# shield_2x_driver.net
KiCad netlist of a schematic drawn in EAGLE
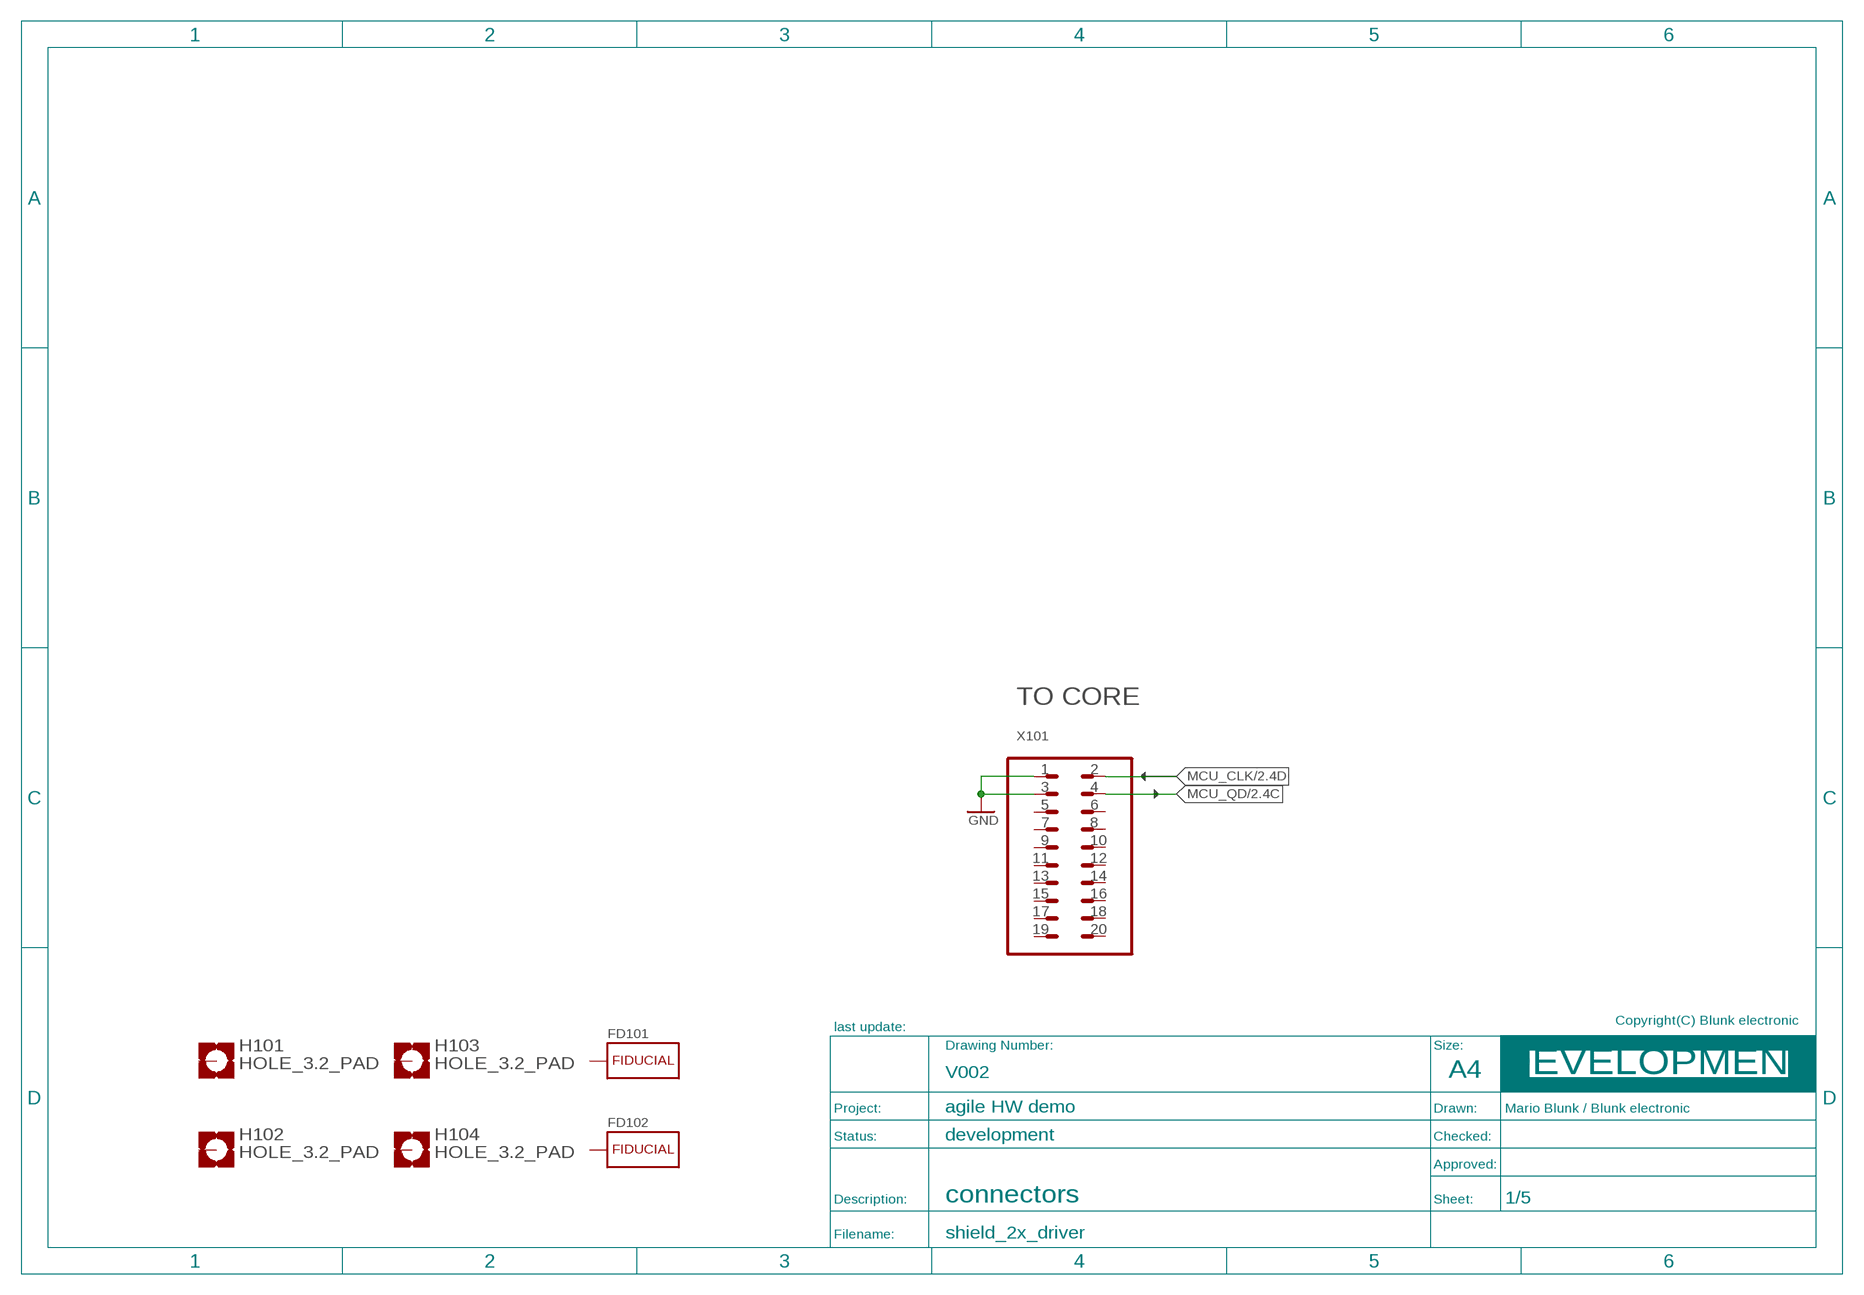
[diagram p0: schematic, sheet 1]
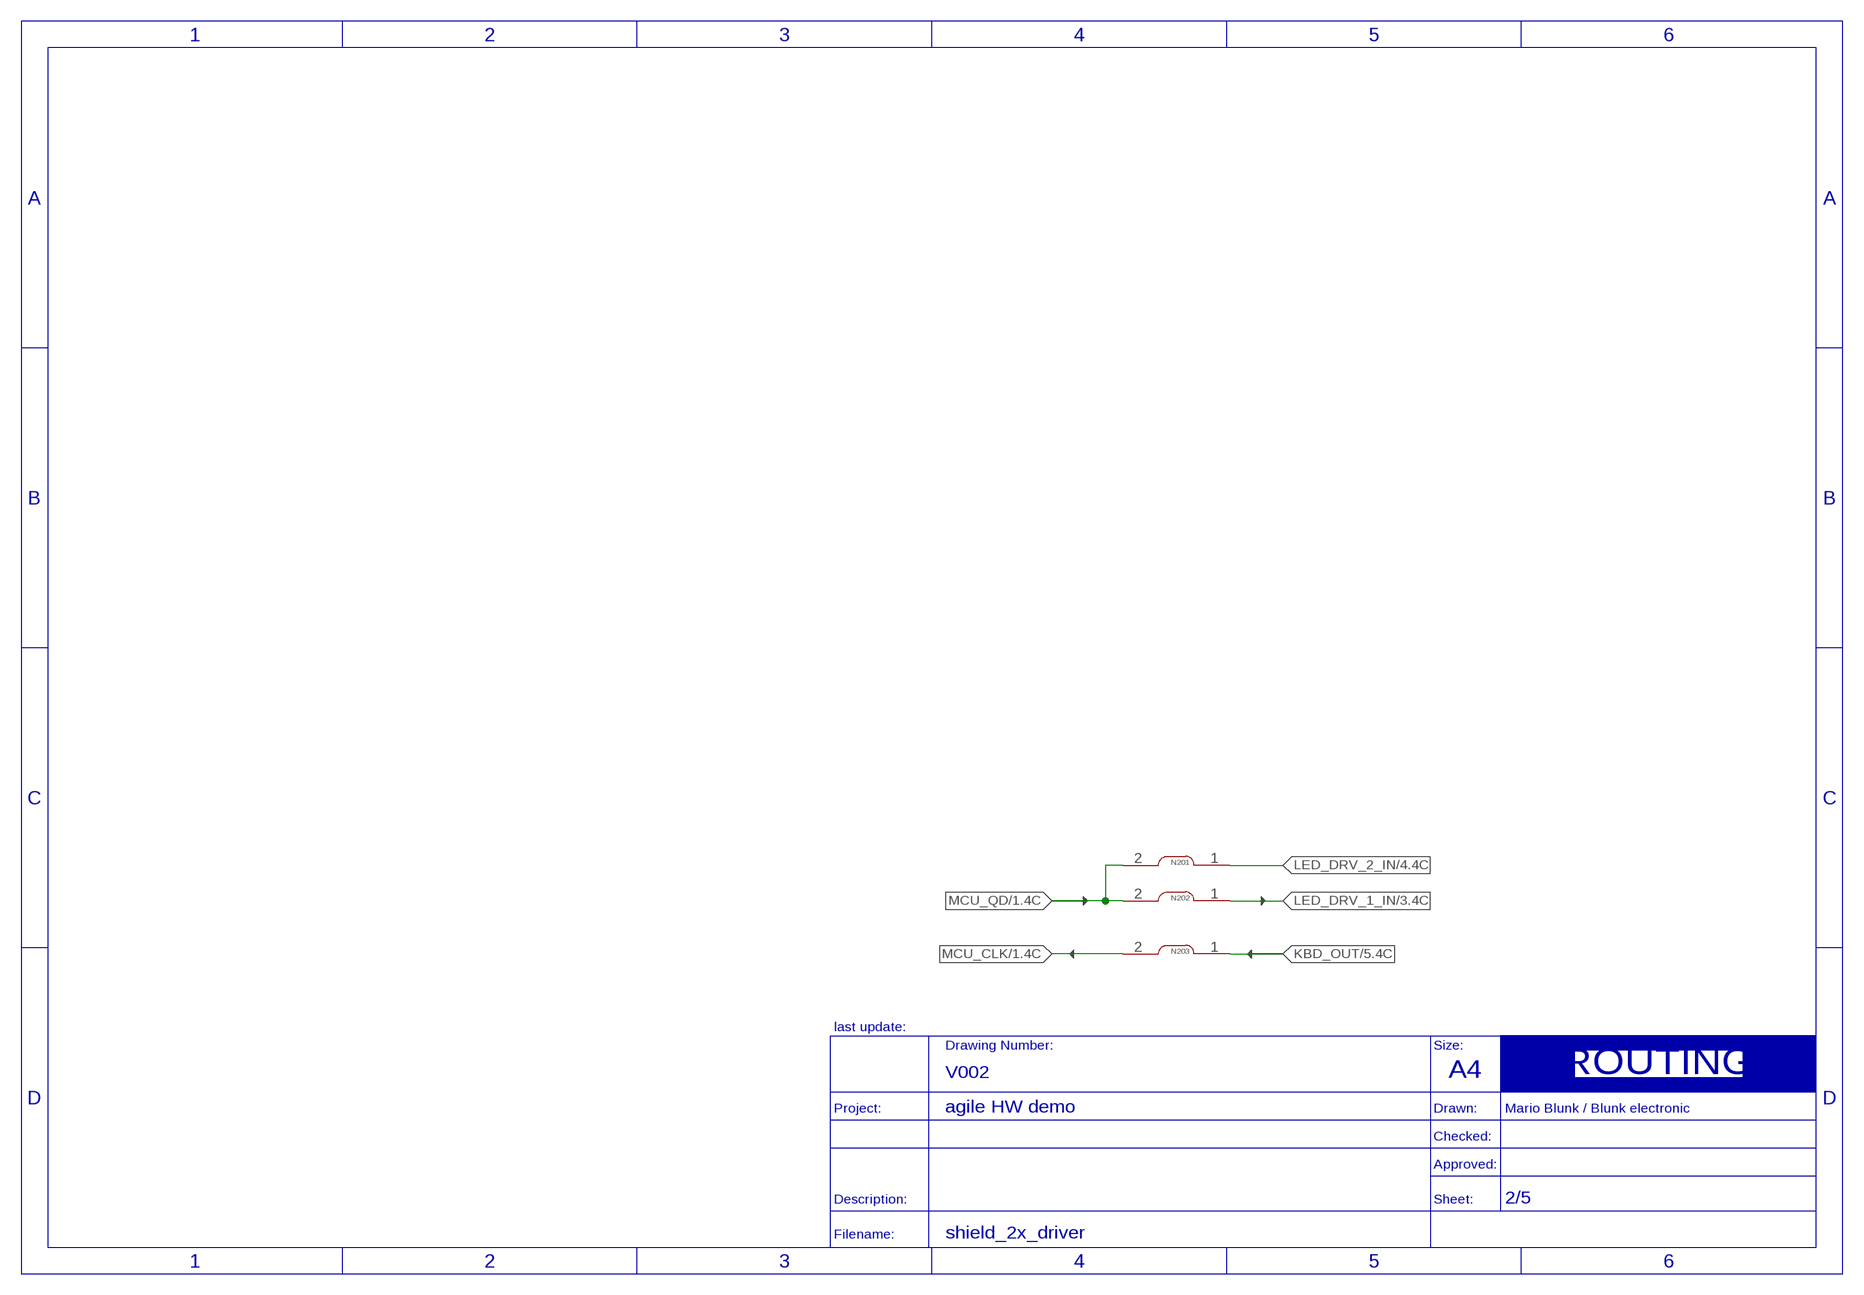
[diagram p1: schematic, sheet 2]
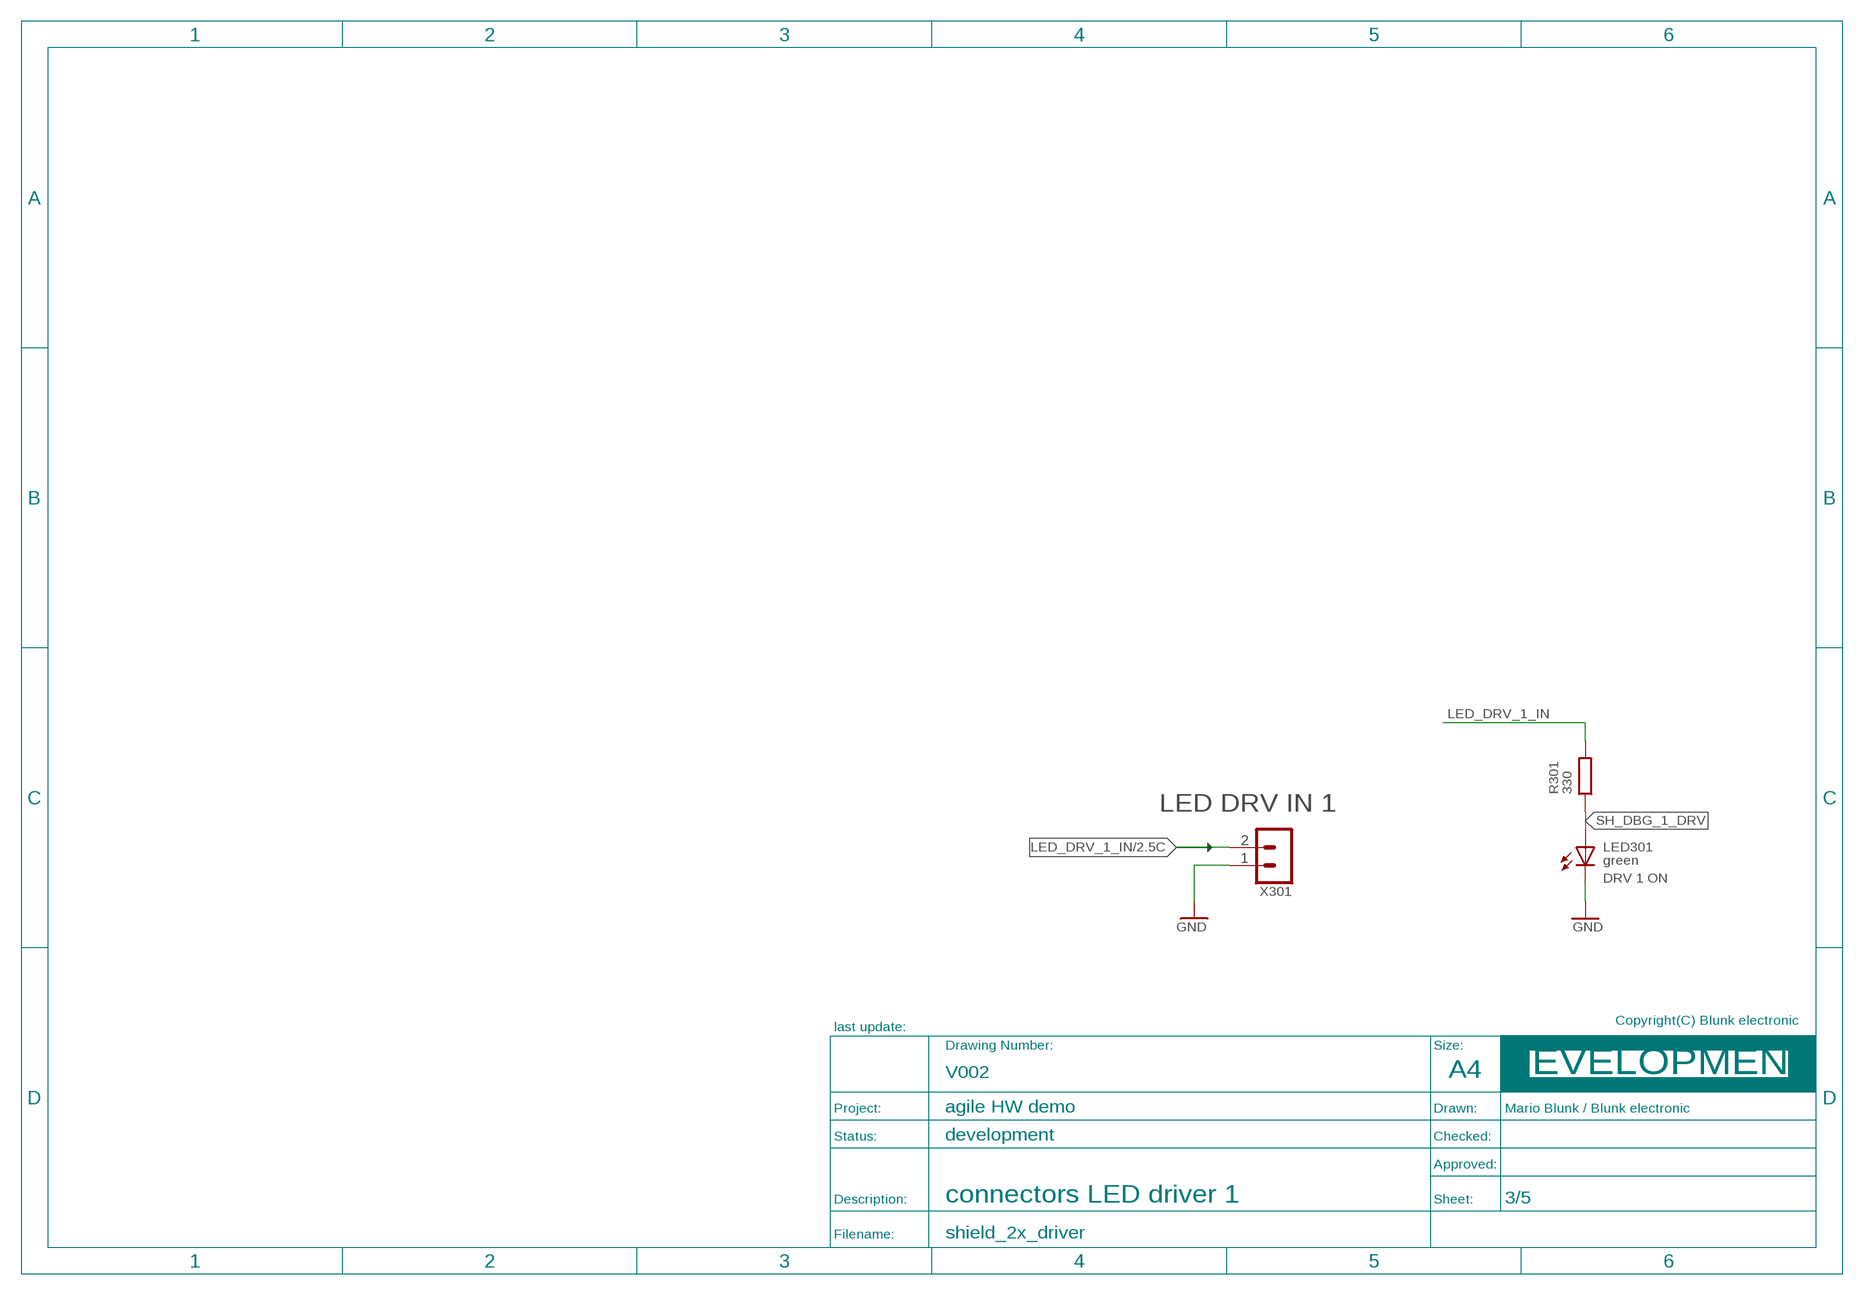
[diagram p2: schematic, sheet 3]
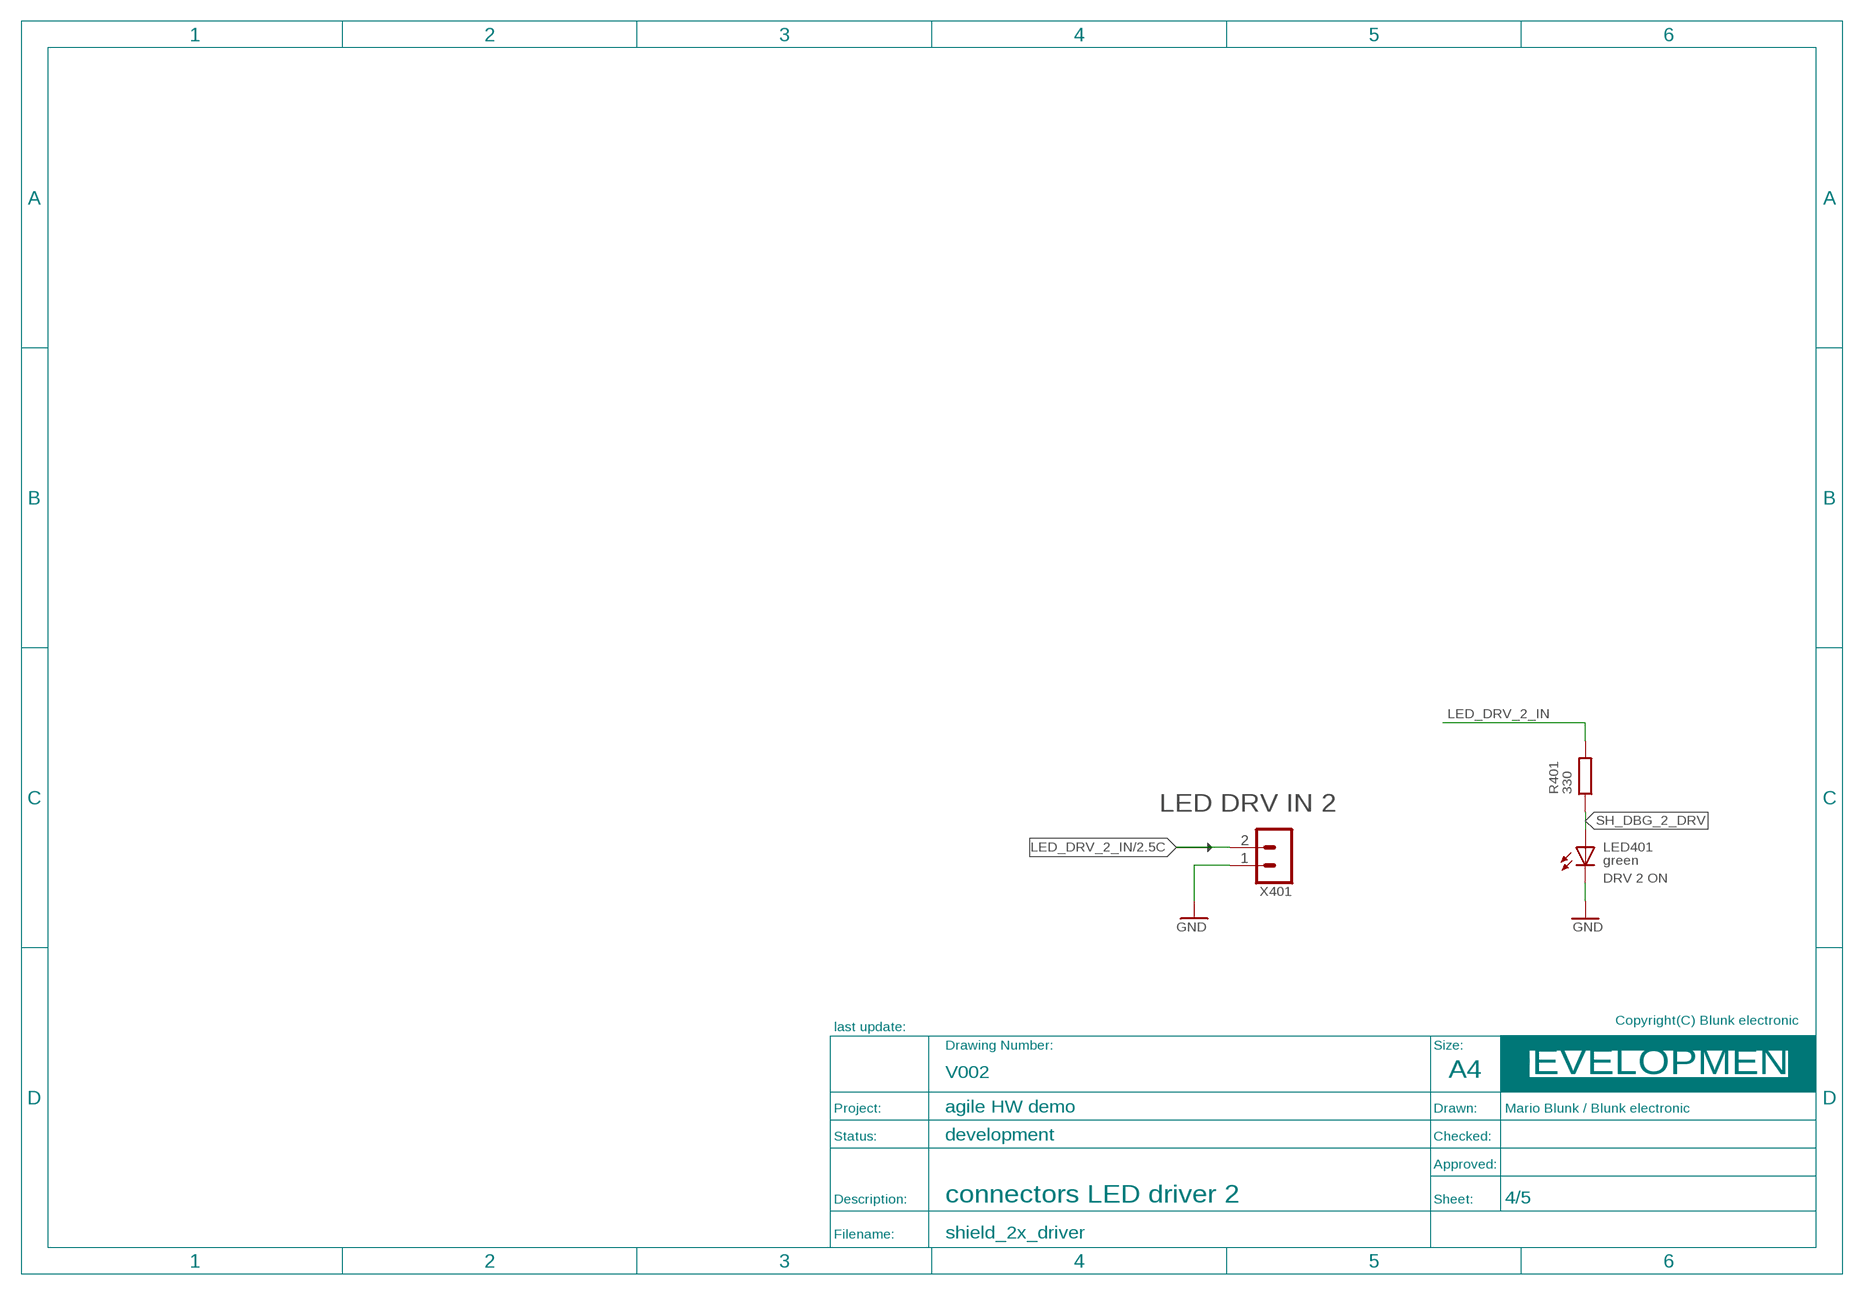
[diagram p3: schematic, sheet 4]
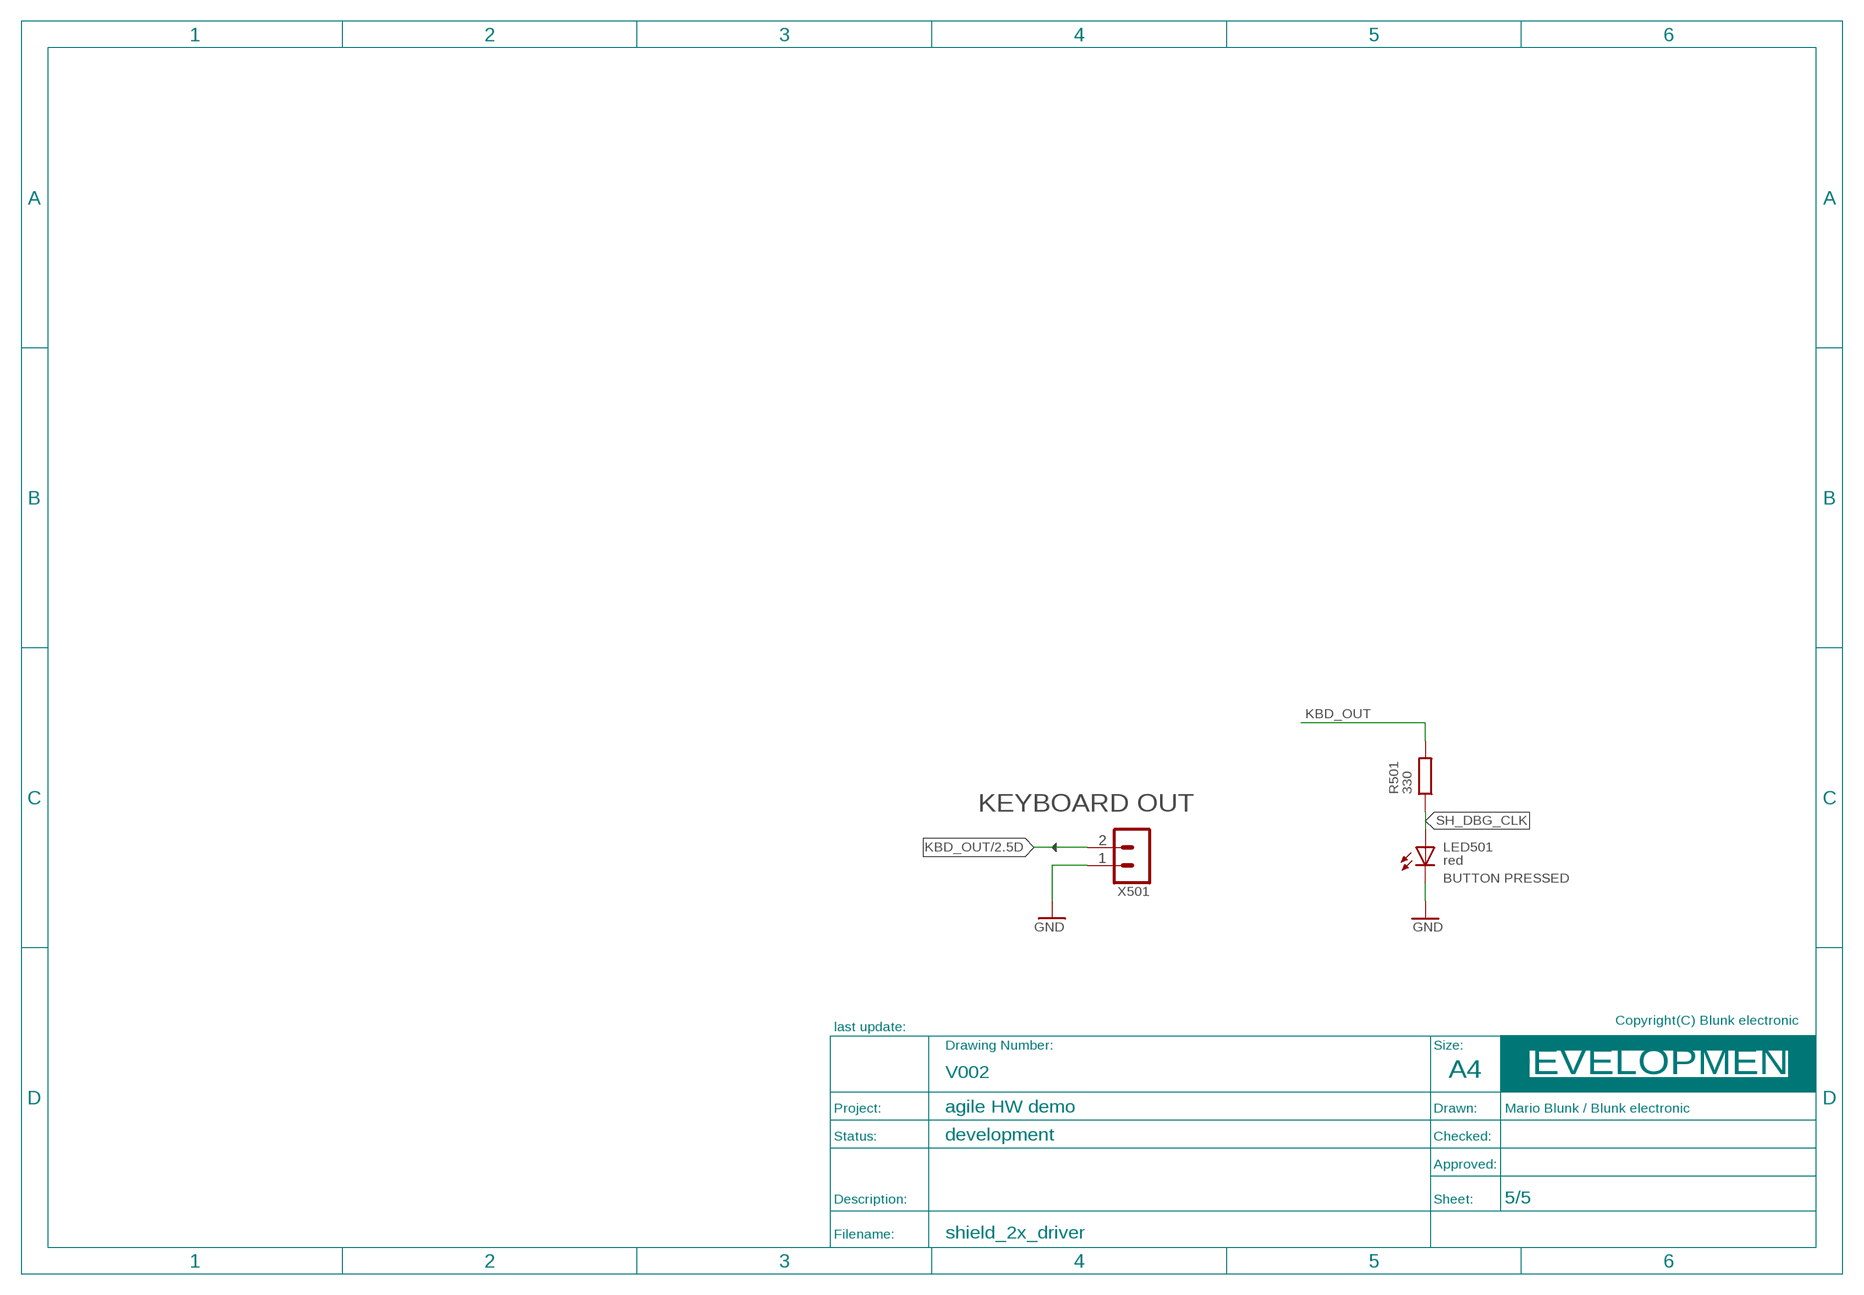
[diagram p4: schematic, sheet 5]

(export (version "E")
  (design (tool "Eeschema 10.0.6"))
  (components
    (comp (ref "LED501")
      (value "red")
      (footprint "eagle-import:S_0805")
      (fields
        (field (name "FUNCTION") "BUTTON PRESSED")
        (field (name "PART_CODE_BEL") "LED_PAC_S_0805_VAL_red")
      )
      (libsource (lib "eagle-import") (part "LED_S_0805"))
    )
    (comp (ref "R501")
      (value "330")
      (footprint "eagle-import:S_0805")
      (fields (field (name "PART_CODE_BEL") "R_PAC_S_0805_VAL_330"))
      (libsource (lib "eagle-import") (part "R_S_0805"))
    )
    (comp (ref "X501")
      (value "MALE_2X1-T-VERTICAL")
      (footprint "eagle-import:T_MALE_2X1_VERTICAL_PITCH_2MM54")
      (fields (field (name "FUNCTION") "KEYBOARD OUT"))
      (libsource (lib "eagle-import") (part "MALE_2X1-T-VERTICAL"))
    )
    (comp (ref "LED401")
      (value "green")
      (footprint "eagle-import:S_0805")
      (fields (field (name "FUNCTION") "DRV 2 ON") (field (name "PART_CODE_BEL") "LED_PAC_S_0805_VAL_green"))
      (libsource (lib "eagle-import") (part "LED_S_0805"))
    )
    (comp (ref "R401")
      (value "330")
      (footprint "eagle-import:S_0805")
      (fields (field (name "PART_CODE_BEL") "R_PAC_S_0805_VAL_330"))
      (libsource (lib "eagle-import") (part "R_S_0805"))
    )
    (comp (ref "X401")
      (value "MALE_2X1-T-VERTICAL")
      (footprint "eagle-import:T_MALE_2X1_VERTICAL_PITCH_2MM54")
      (fields (field (name "FUNCTION") "LED DRV IN 2"))
      (libsource (lib "eagle-import") (part "MALE_2X1-T-VERTICAL"))
    )
    (comp (ref "LED301")
      (value "green")
      (footprint "eagle-import:S_0805")
      (fields (field (name "FUNCTION") "DRV 1 ON") (field (name "PART_CODE_BEL") "LED_PAC_S_0805_VAL_green"))
      (libsource (lib "eagle-import") (part "LED_S_0805"))
    )
    (comp (ref "R301")
      (value "330")
      (footprint "eagle-import:S_0805")
      (fields (field (name "PART_CODE_BEL") "R_PAC_S_0805_VAL_330"))
      (libsource (lib "eagle-import") (part "R_S_0805"))
    )
    (comp (ref "X301")
      (value "MALE_2X1-T-VERTICAL")
      (footprint "eagle-import:T_MALE_2X1_VERTICAL_PITCH_2MM54")
      (fields (field (name "FUNCTION") "LED DRV IN 1"))
      (libsource (lib "eagle-import") (part "MALE_2X1-T-VERTICAL"))
    )
    (comp (ref "N201")
      (value "NET_CHANGER-S-0.3MM")
      (footprint "eagle-import:S_NET_CHANGER_0.3MM")
      (libsource (lib "eagle-import") (part "NET_CHANGER-S-0.3MM"))
    )
    (comp (ref "N202")
      (value "NET_CHANGER-S-0.3MM")
      (footprint "eagle-import:S_NET_CHANGER_0.3MM")
      (libsource (lib "eagle-import") (part "NET_CHANGER-S-0.3MM"))
    )
    (comp (ref "N203")
      (value "NET_CHANGER-S-0.15MM")
      (footprint "eagle-import:S_NET_CHANGER_0.15MM")
      (libsource (lib "eagle-import") (part "NET_CHANGER-S-0.15MM"))
    )
    (comp (ref "FD101")
      (value "FIDUCIAL_CROSSHAIR")
      (footprint "eagle-import:CROSSHAIR")
      (libsource (lib "eagle-import") (part "FIDUCIAL_CROSSHAIR"))
    )
    (comp (ref "FD102")
      (value "FIDUCIAL_CROSSHAIR")
      (footprint "eagle-import:CROSSHAIR")
      (libsource (lib "eagle-import") (part "FIDUCIAL_CROSSHAIR"))
    )
    (comp (ref "H101")
      (value "HOLE_3.2_PAD")
      (footprint "eagle-import:3.2_PAD")
      (libsource (lib "eagle-import") (part "HOLE_3.2_PAD"))
    )
    (comp (ref "H102")
      (value "HOLE_3.2_PAD")
      (footprint "eagle-import:3.2_PAD")
      (libsource (lib "eagle-import") (part "HOLE_3.2_PAD"))
    )
    (comp (ref "H103")
      (value "HOLE_3.2_PAD")
      (footprint "eagle-import:3.2_PAD")
      (libsource (lib "eagle-import") (part "HOLE_3.2_PAD"))
    )
    (comp (ref "H104")
      (value "HOLE_3.2_PAD")
      (footprint "eagle-import:3.2_PAD")
      (libsource (lib "eagle-import") (part "HOLE_3.2_PAD"))
    )
    (comp (ref "X101")
      (value "MALE_2X10-T-VERTICAL_2.54MM")
      (footprint "eagle-import:T_MALE_2X10_VERTICAL_GRID_2.54MM")
      (fields
        (field (name "FUNCTION") "TO CORE")
        (field (name "PART_CODE_BEL") "X_PAC_T_MALE_2X10_VERTICAL_PITCH_2mm54")
      )
      (libsource (lib "eagle-import") (part "MALE_2X10-T-VERTICAL_2.54MM"))
    )
  )
  (nets
    (net (code "1") (name "GND") (class "Default")
      (node (ref "LED301") (pin "C") (pinfunction "C_C") (pintype "passive"))
      (node (ref "LED401") (pin "C") (pinfunction "C_C") (pintype "passive"))
      (node (ref "LED501") (pin "C") (pinfunction "C_C") (pintype "passive"))
      (node (ref "X101") (pin "1") (pinfunction "1_1") (pintype "passive"))
      (node (ref "X101") (pin "3") (pinfunction "3_3") (pintype "passive"))
      (node (ref "X301") (pin "1") (pinfunction "1_1") (pintype "passive"))
      (node (ref "X401") (pin "1") (pinfunction "1_1") (pintype "passive"))
      (node (ref "X501") (pin "1") (pinfunction "1_1") (pintype "passive"))
    )
    (net (code "2") (name "KBD_OUT") (class "Default")
      (node (ref "N203") (pin "1") (pinfunction "1_1") (pintype "passive"))
      (node (ref "R501") (pin "2") (pinfunction "2_2") (pintype "passive"))
      (node (ref "X501") (pin "2") (pinfunction "2_2") (pintype "passive"))
    )
    (net (code "3") (name "LED_DRV_1_IN") (class "Default")
      (node (ref "N202") (pin "1") (pinfunction "1_1") (pintype "passive"))
      (node (ref "R301") (pin "2") (pinfunction "2_2") (pintype "passive"))
      (node (ref "X301") (pin "2") (pinfunction "2_2") (pintype "passive"))
    )
    (net (code "4") (name "LED_DRV_2_IN") (class "Default")
      (node (ref "N201") (pin "1") (pinfunction "1_1") (pintype "passive"))
      (node (ref "R401") (pin "2") (pinfunction "2_2") (pintype "passive"))
      (node (ref "X401") (pin "2") (pinfunction "2_2") (pintype "passive"))
    )
    (net (code "5") (name "MCU_CLK") (class "Default")
      (node (ref "N203") (pin "2") (pinfunction "2_2") (pintype "passive"))
      (node (ref "X101") (pin "2") (pinfunction "2_2") (pintype "passive"))
    )
    (net (code "6") (name "MCU_QD") (class "Default")
      (node (ref "N201") (pin "2") (pinfunction "2_2") (pintype "passive"))
      (node (ref "N202") (pin "2") (pinfunction "2_2") (pintype "passive"))
      (node (ref "X101") (pin "4") (pinfunction "4_4") (pintype "passive"))
    )
    (net (code "7") (name "SH_DBG_1_DRV") (class "Default")
      (node (ref "LED301") (pin "A") (pinfunction "A_A") (pintype "passive"))
      (node (ref "R301") (pin "1") (pinfunction "1_1") (pintype "passive"))
    )
    (net (code "8") (name "SH_DBG_2_DRV") (class "Default")
      (node (ref "LED401") (pin "A") (pinfunction "A_A") (pintype "passive"))
      (node (ref "R401") (pin "1") (pinfunction "1_1") (pintype "passive"))
    )
    (net (code "9") (name "SH_DBG_CLK") (class "Default")
      (node (ref "LED501") (pin "A") (pinfunction "A_A") (pintype "passive"))
      (node (ref "R501") (pin "1") (pinfunction "1_1") (pintype "passive"))
    )
    (net (code "10") (name "unconnected-(FD101-NC-Pad1)") (class "Default")
      (node (ref "FD101") (pin "1") (pinfunction "NC_1") (pintype "no_connect"))
    )
    (net (code "11") (name "unconnected-(FD102-NC-Pad1)") (class "Default")
      (node (ref "FD102") (pin "1") (pinfunction "NC_1") (pintype "no_connect"))
    )
    (net (code "12") (name "unconnected-(H101-MOUNT-PadH1)") (class "Default")
      (node (ref "H101") (pin "H1") (pinfunction "MOUNT_H1") (pintype "passive"))
    )
    (net (code "13") (name "unconnected-(H102-MOUNT-PadH1)") (class "Default")
      (node (ref "H102") (pin "H1") (pinfunction "MOUNT_H1") (pintype "passive"))
    )
    (net (code "14") (name "unconnected-(H103-MOUNT-PadH1)") (class "Default")
      (node (ref "H103") (pin "H1") (pinfunction "MOUNT_H1") (pintype "passive"))
    )
    (net (code "15") (name "unconnected-(H104-MOUNT-PadH1)") (class "Default")
      (node (ref "H104") (pin "H1") (pinfunction "MOUNT_H1") (pintype "passive"))
    )
    (net (code "16") (name "unconnected-(X101-Pad5)") (class "Default")
      (node (ref "X101") (pin "5") (pinfunction "5_5") (pintype "passive"))
    )
    (net (code "17") (name "unconnected-(X101-Pad6)") (class "Default")
      (node (ref "X101") (pin "6") (pinfunction "6_6") (pintype "passive"))
    )
    (net (code "18") (name "unconnected-(X101-Pad7)") (class "Default")
      (node (ref "X101") (pin "7") (pinfunction "7_7") (pintype "passive"))
    )
    (net (code "19") (name "unconnected-(X101-Pad8)") (class "Default")
      (node (ref "X101") (pin "8") (pinfunction "8_8") (pintype "passive"))
    )
    (net (code "20") (name "unconnected-(X101-Pad9)") (class "Default")
      (node (ref "X101") (pin "9") (pinfunction "9_9") (pintype "passive"))
    )
    (net (code "21") (name "unconnected-(X101-Pad10)") (class "Default")
      (node (ref "X101") (pin "10") (pinfunction "10_10") (pintype "passive"))
    )
    (net (code "22") (name "unconnected-(X101-Pad11)") (class "Default")
      (node (ref "X101") (pin "11") (pinfunction "11_11") (pintype "passive"))
    )
    (net (code "23") (name "unconnected-(X101-Pad12)") (class "Default")
      (node (ref "X101") (pin "12") (pinfunction "12_12") (pintype "passive"))
    )
    (net (code "24") (name "unconnected-(X101-Pad13)") (class "Default")
      (node (ref "X101") (pin "13") (pinfunction "13_13") (pintype "passive"))
    )
    (net (code "25") (name "unconnected-(X101-Pad14)") (class "Default")
      (node (ref "X101") (pin "14") (pinfunction "14_14") (pintype "passive"))
    )
    (net (code "26") (name "unconnected-(X101-Pad15)") (class "Default")
      (node (ref "X101") (pin "15") (pinfunction "15_15") (pintype "passive"))
    )
    (net (code "27") (name "unconnected-(X101-Pad16)") (class "Default")
      (node (ref "X101") (pin "16") (pinfunction "16_16") (pintype "passive"))
    )
    (net (code "28") (name "unconnected-(X101-Pad17)") (class "Default")
      (node (ref "X101") (pin "17") (pinfunction "17_17") (pintype "passive"))
    )
    (net (code "29") (name "unconnected-(X101-Pad18)") (class "Default")
      (node (ref "X101") (pin "18") (pinfunction "18_18") (pintype "passive"))
    )
    (net (code "30") (name "unconnected-(X101-Pad19)") (class "Default")
      (node (ref "X101") (pin "19") (pinfunction "19_19") (pintype "passive"))
    )
    (net (code "31") (name "unconnected-(X101-Pad20)") (class "Default")
      (node (ref "X101") (pin "20") (pinfunction "20_20") (pintype "passive"))
    )
  )
)
